# 4_Connectors.net
KiCad netlist of a schematic drawn in Altium Designer
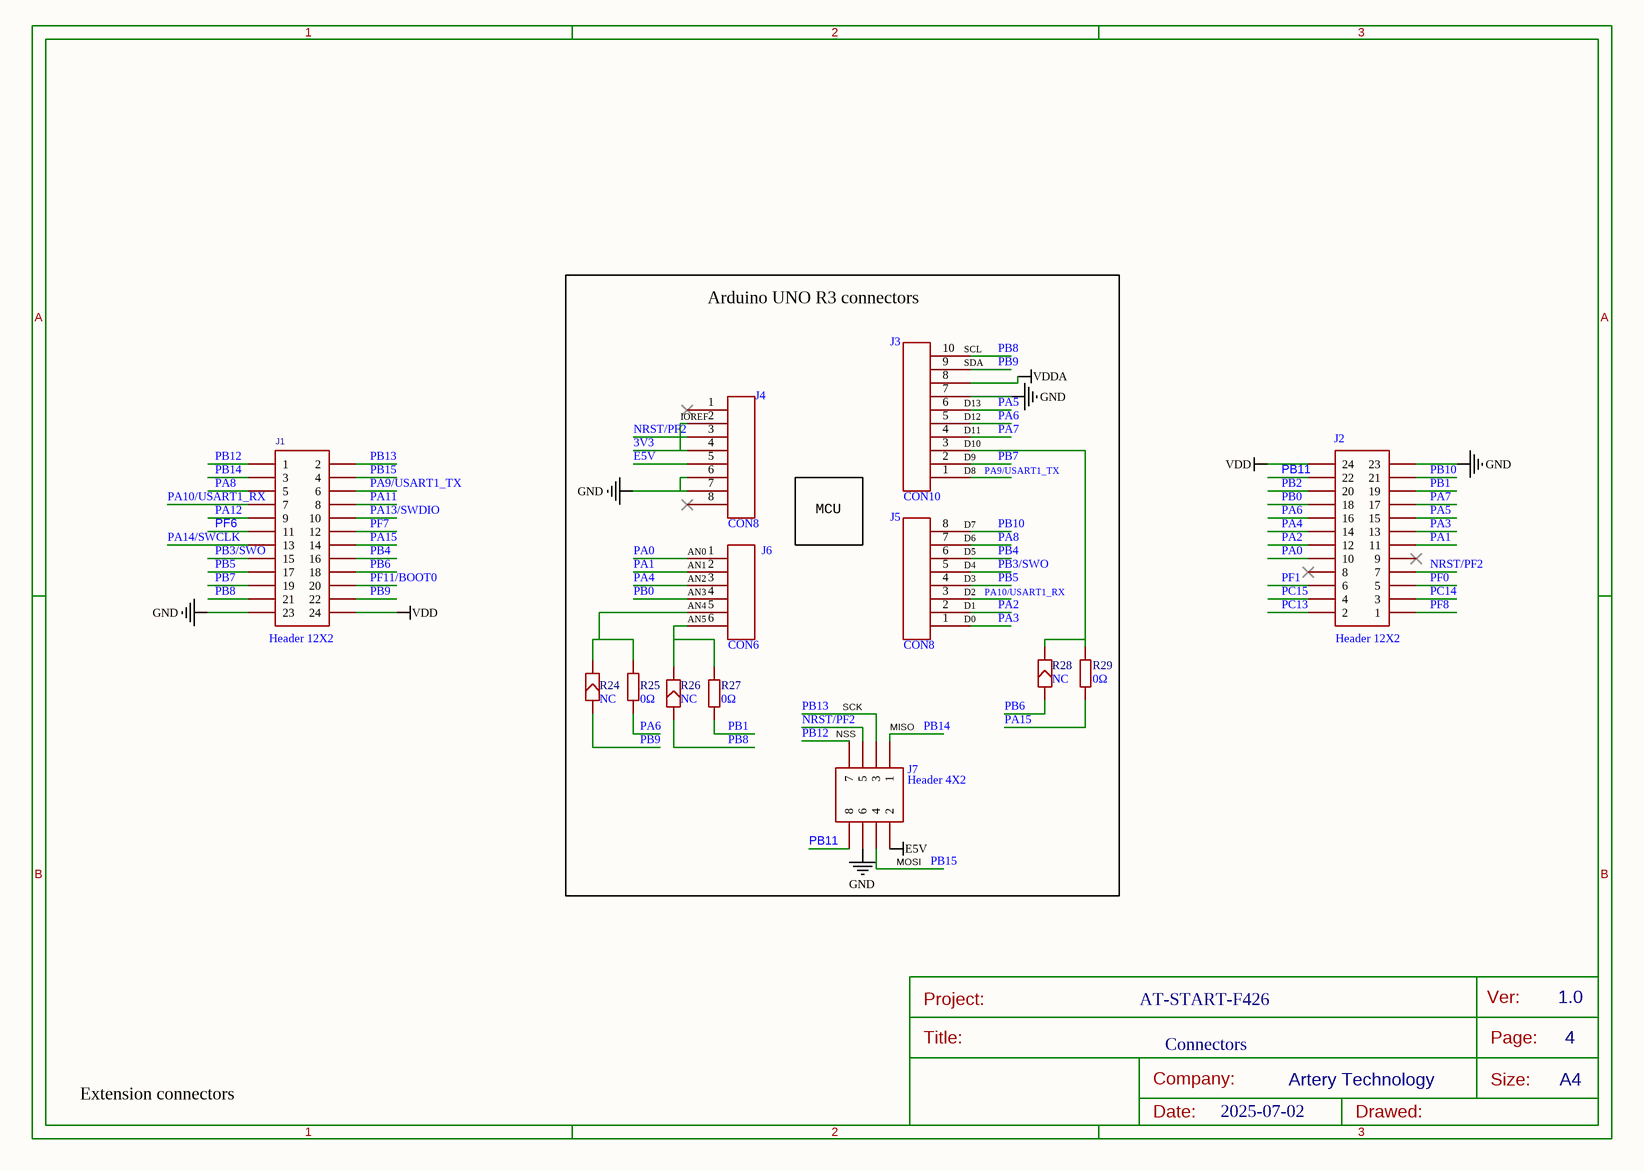
[diagram p0: 4_Connectors.schdoc]

(export (version "E")
  (design (tool "Eeschema 10.0.6"))
  (components
    (comp (ref "J1")
      (value "Header 12X2")
      (footprint "HEAD2*12")
      (fields (field (name "PUBLISHER") "Altium Limited"))
      (libsource (lib "altium-import") (part "root_0_Header 12X2_"))
    )
    (comp (ref "J2")
      (value "Header 12X2")
      (footprint "HEAD2*12")
      (fields (field (name "PUBLISHER") "Altium Limited"))
      (libsource (lib "altium-import") (part "root_2_Header 12X2_"))
    )
    (comp (ref "J3")
      (value "CON10")
      (footprint "HDR1X10 - 2#")
      (libsource (lib "altium-import") (part "root_2_CON10_"))
    )
    (comp (ref "J4")
      (value "CON8")
      (footprint "HDR1X8 - 2#")
      (libsource (lib "altium-import") (part "root_0_CON8_"))
    )
    (comp (ref "J5")
      (value "CON8")
      (footprint "HDR1X8 - 2#")
      (libsource (lib "altium-import") (part "root_2_CON8_"))
    )
    (comp (ref "J6")
      (value "CON6")
      (footprint "HDR1X6 -2#")
      (libsource (lib "altium-import") (part "root_0_CON6_"))
    )
    (comp (ref "J7")
      (value "Header 4X2")
      (footprint "HDR2X4")
      (fields (field (name "PUBLISHER") "Altium Limited"))
      (libsource (lib "altium-import") (part "root_3_Header 4X2_"))
    )
    (comp (ref "R24")
      (value "NC")
      (footprint "SB-PAD_2")
      (libsource (lib "altium-import") (part "root_1_SB_PAD_"))
    )
    (comp (ref "R25")
      (value "0Ω")
      (footprint "SB-PAD_2")
      (fields
        (field (name "MANUFACTURER") "UNI-ROYAL(厚声)")
        (field (name "MANUFACTURER PART") "0603WAF0000T5E")
        (field (name "TOLERANCE") "±1%")
      )
      (libsource (lib "altium-import") (part "root_1_0603WAF0000T5E_"))
    )
    (comp (ref "R26")
      (value "NC")
      (footprint "SB-PAD_2")
      (libsource (lib "altium-import") (part "root_1_SB_PAD_"))
    )
    (comp (ref "R27")
      (value "0Ω")
      (footprint "SB-PAD_2")
      (fields
        (field (name "MANUFACTURER") "UNI-ROYAL(厚声)")
        (field (name "MANUFACTURER PART") "0603WAF0000T5E")
        (field (name "TOLERANCE") "±1%")
      )
      (libsource (lib "altium-import") (part "root_1_0603WAF0000T5E_"))
    )
    (comp (ref "R28")
      (value "NC")
      (footprint "SB-PAD_2")
      (libsource (lib "altium-import") (part "root_1_SB_PAD_"))
    )
    (comp (ref "R29")
      (value "0Ω")
      (footprint "SB-PAD_2")
      (fields
        (field (name "MANUFACTURER") "UNI-ROYAL(厚声)")
        (field (name "MANUFACTURER PART") "0603WAF0000T5E")
        (field (name "TOLERANCE") "±1%")
      )
      (libsource (lib "altium-import") (part "root_1_0603WAF0000T5E_"))
    )
  )
  (nets
    (net (code "1") (name "/3V3") (class "Default")
      (node (ref "J4") (pin "2") (pinfunction "2_2") (pintype "passive"))
      (node (ref "J4") (pin "4") (pinfunction "4_4") (pintype "passive"))
    )
    (net (code "2") (name "/NRST{slash}PF2") (class "Default")
      (node (ref "J2") (pin "7") (pinfunction "7_7") (pintype "passive"))
      (node (ref "J4") (pin "3") (pinfunction "3_3") (pintype "passive"))
      (node (ref "J7") (pin "5") (pinfunction "5_5") (pintype "passive"))
    )
    (net (code "3") (name "/PA0") (class "Default")
      (node (ref "J2") (pin "10") (pinfunction "10_10") (pintype "passive"))
      (node (ref "J6") (pin "1") (pinfunction "1_1") (pintype "passive"))
    )
    (net (code "4") (name "/PA1") (class "Default")
      (node (ref "J2") (pin "11") (pinfunction "11_11") (pintype "passive"))
      (node (ref "J6") (pin "2") (pinfunction "2_2") (pintype "passive"))
    )
    (net (code "5") (name "/PA2") (class "Default")
      (node (ref "J2") (pin "12") (pinfunction "12_12") (pintype "passive"))
      (node (ref "J5") (pin "2") (pinfunction "2_2") (pintype "passive"))
    )
    (net (code "6") (name "/PA3") (class "Default")
      (node (ref "J2") (pin "13") (pinfunction "13_13") (pintype "passive"))
      (node (ref "J5") (pin "1") (pinfunction "1_1") (pintype "passive"))
    )
    (net (code "7") (name "/PA4") (class "Default")
      (node (ref "J2") (pin "14") (pinfunction "14_14") (pintype "passive"))
      (node (ref "J6") (pin "3") (pinfunction "3_3") (pintype "passive"))
    )
    (net (code "8") (name "/PA5") (class "Default")
      (node (ref "J2") (pin "15") (pinfunction "15_15") (pintype "passive"))
      (node (ref "J3") (pin "6") (pinfunction "6_6") (pintype "passive"))
    )
    (net (code "9") (name "/PA6") (class "Default")
      (node (ref "J2") (pin "16") (pinfunction "16_16") (pintype "passive"))
      (node (ref "J3") (pin "5") (pinfunction "5_5") (pintype "passive"))
      (node (ref "R25") (pin "1") (pinfunction "1_1") (pintype "passive"))
    )
    (net (code "10") (name "/PA7") (class "Default")
      (node (ref "J2") (pin "17") (pinfunction "17_17") (pintype "passive"))
      (node (ref "J3") (pin "4") (pinfunction "4_4") (pintype "passive"))
    )
    (net (code "11") (name "/PA8") (class "Default")
      (node (ref "J1") (pin "5") (pinfunction "5_5") (pintype "passive"))
      (node (ref "J5") (pin "7") (pinfunction "7_7") (pintype "passive"))
    )
    (net (code "12") (name "/PA9{slash}USART1_TX") (class "Default")
      (node (ref "J1") (pin "6") (pinfunction "6_6") (pintype "passive"))
      (node (ref "J3") (pin "1") (pinfunction "1_1") (pintype "passive"))
    )
    (net (code "13") (name "/PA10{slash}USART1_RX") (class "Default")
      (node (ref "J1") (pin "7") (pinfunction "7_7") (pintype "passive"))
      (node (ref "J5") (pin "3") (pinfunction "3_3") (pintype "passive"))
    )
    (net (code "14") (name "/PA11") (class "Default")
      (node (ref "J1") (pin "8") (pinfunction "8_8") (pintype "passive"))
    )
    (net (code "15") (name "/PA12") (class "Default")
      (node (ref "J1") (pin "9") (pinfunction "9_9") (pintype "passive"))
    )
    (net (code "16") (name "/PA13{slash}SWDIO") (class "Default")
      (node (ref "J1") (pin "10") (pinfunction "10_10") (pintype "passive"))
    )
    (net (code "17") (name "/PA14{slash}SWCLK") (class "Default")
      (node (ref "J1") (pin "13") (pinfunction "13_13") (pintype "passive"))
    )
    (net (code "18") (name "/PA15") (class "Default")
      (node (ref "J1") (pin "14") (pinfunction "14_14") (pintype "passive"))
      (node (ref "R29") (pin "1") (pinfunction "1_1") (pintype "passive"))
    )
    (net (code "19") (name "/PB0") (class "Default")
      (node (ref "J2") (pin "18") (pinfunction "18_18") (pintype "passive"))
      (node (ref "J6") (pin "4") (pinfunction "4_4") (pintype "passive"))
    )
    (net (code "20") (name "/PB1") (class "Default")
      (node (ref "J2") (pin "19") (pinfunction "19_19") (pintype "passive"))
      (node (ref "R27") (pin "1") (pinfunction "1_1") (pintype "passive"))
    )
    (net (code "21") (name "/PB2") (class "Default")
      (node (ref "J2") (pin "20") (pinfunction "20_20") (pintype "passive"))
    )
    (net (code "22") (name "/PB3{slash}SWO") (class "Default")
      (node (ref "J1") (pin "15") (pinfunction "15_15") (pintype "passive"))
      (node (ref "J5") (pin "5") (pinfunction "5_5") (pintype "passive"))
    )
    (net (code "23") (name "/PB4") (class "Default")
      (node (ref "J1") (pin "16") (pinfunction "16_16") (pintype "passive"))
      (node (ref "J5") (pin "6") (pinfunction "6_6") (pintype "passive"))
    )
    (net (code "24") (name "/PB5") (class "Default")
      (node (ref "J1") (pin "17") (pinfunction "17_17") (pintype "passive"))
      (node (ref "J5") (pin "4") (pinfunction "4_4") (pintype "passive"))
    )
    (net (code "25") (name "/PB6") (class "Default")
      (node (ref "J1") (pin "18") (pinfunction "18_18") (pintype "passive"))
      (node (ref "R28") (pin "1") (pinfunction "1_1") (pintype "passive"))
    )
    (net (code "26") (name "/PB7") (class "Default")
      (node (ref "J1") (pin "19") (pinfunction "19_19") (pintype "passive"))
      (node (ref "J3") (pin "2") (pinfunction "2_2") (pintype "passive"))
    )
    (net (code "27") (name "/PB8") (class "Default")
      (node (ref "J1") (pin "21") (pinfunction "21_21") (pintype "passive"))
      (node (ref "J3") (pin "10") (pinfunction "10_10") (pintype "passive"))
      (node (ref "R26") (pin "1") (pinfunction "1_1") (pintype "passive"))
    )
    (net (code "28") (name "/PB9") (class "Default")
      (node (ref "J1") (pin "22") (pinfunction "22_22") (pintype "passive"))
      (node (ref "J3") (pin "9") (pinfunction "9_9") (pintype "passive"))
      (node (ref "R24") (pin "1") (pinfunction "1_1") (pintype "passive"))
    )
    (net (code "29") (name "/PB10") (class "Default")
      (node (ref "J2") (pin "21") (pinfunction "21_21") (pintype "passive"))
      (node (ref "J5") (pin "8") (pinfunction "8_8") (pintype "passive"))
    )
    (net (code "30") (name "/PB11") (class "Default")
      (node (ref "J2") (pin "22") (pinfunction "22_22") (pintype "passive"))
      (node (ref "J7") (pin "8") (pinfunction "8_8") (pintype "passive"))
    )
    (net (code "31") (name "/PB12") (class "Default")
      (node (ref "J1") (pin "1") (pinfunction "1_1") (pintype "passive"))
      (node (ref "J7") (pin "7") (pinfunction "7_7") (pintype "passive"))
    )
    (net (code "32") (name "/PB13") (class "Default")
      (node (ref "J1") (pin "2") (pinfunction "2_2") (pintype "passive"))
      (node (ref "J7") (pin "3") (pinfunction "3_3") (pintype "passive"))
    )
    (net (code "33") (name "/PB14") (class "Default")
      (node (ref "J1") (pin "3") (pinfunction "3_3") (pintype "passive"))
      (node (ref "J7") (pin "1") (pinfunction "1_1") (pintype "passive"))
    )
    (net (code "34") (name "/PB15") (class "Default")
      (node (ref "J1") (pin "4") (pinfunction "4_4") (pintype "passive"))
      (node (ref "J7") (pin "4") (pinfunction "4_4") (pintype "passive"))
    )
    (net (code "35") (name "/PC13") (class "Default")
      (node (ref "J2") (pin "2") (pinfunction "2_2") (pintype "passive"))
    )
    (net (code "36") (name "/PC14") (class "Default")
      (node (ref "J2") (pin "3") (pinfunction "3_3") (pintype "passive"))
    )
    (net (code "37") (name "/PC15") (class "Default")
      (node (ref "J2") (pin "4") (pinfunction "4_4") (pintype "passive"))
    )
    (net (code "38") (name "/PF0") (class "Default")
      (node (ref "J2") (pin "5") (pinfunction "5_5") (pintype "passive"))
    )
    (net (code "39") (name "/PF1") (class "Default")
      (node (ref "J2") (pin "6") (pinfunction "6_6") (pintype "passive"))
    )
    (net (code "40") (name "/PF6") (class "Default")
      (node (ref "J1") (pin "11") (pinfunction "11_11") (pintype "passive"))
    )
    (net (code "41") (name "/PF7") (class "Default")
      (node (ref "J1") (pin "12") (pinfunction "12_12") (pintype "passive"))
    )
    (net (code "42") (name "/PF8") (class "Default")
      (node (ref "J2") (pin "1") (pinfunction "1_1") (pintype "passive"))
    )
    (net (code "43") (name "/PF11{slash}BOOT0") (class "Default")
      (node (ref "J1") (pin "20") (pinfunction "20_20") (pintype "passive"))
    )
    (net (code "44") (name "E5V") (class "Default")
      (node (ref "J4") (pin "5") (pinfunction "5_5") (pintype "passive"))
      (node (ref "J7") (pin "2") (pinfunction "2_2") (pintype "passive"))
    )
    (net (code "45") (name "GND") (class "Default")
      (node (ref "J1") (pin "23") (pinfunction "23_23") (pintype "passive"))
      (node (ref "J2") (pin "23") (pinfunction "23_23") (pintype "passive"))
      (node (ref "J3") (pin "7") (pinfunction "7_7") (pintype "passive"))
      (node (ref "J4") (pin "6") (pinfunction "6_6") (pintype "passive"))
      (node (ref "J4") (pin "7") (pinfunction "7_7") (pintype "passive"))
      (node (ref "J7") (pin "6") (pinfunction "6_6") (pintype "passive"))
    )
    (net (code "46") (name "Net-(J3-Pad3)") (class "Default")
      (node (ref "J3") (pin "3") (pinfunction "3_3") (pintype "passive"))
      (node (ref "R28") (pin "2") (pinfunction "2_2") (pintype "passive"))
      (node (ref "R29") (pin "2") (pinfunction "2_2") (pintype "passive"))
    )
    (net (code "47") (name "Net-(J6-Pad5)") (class "Default")
      (node (ref "J6") (pin "5") (pinfunction "5_5") (pintype "passive"))
      (node (ref "R24") (pin "2") (pinfunction "2_2") (pintype "passive"))
      (node (ref "R25") (pin "2") (pinfunction "2_2") (pintype "passive"))
    )
    (net (code "48") (name "Net-(J6-Pad6)") (class "Default")
      (node (ref "J6") (pin "6") (pinfunction "6_6") (pintype "passive"))
      (node (ref "R26") (pin "2") (pinfunction "2_2") (pintype "passive"))
      (node (ref "R27") (pin "2") (pinfunction "2_2") (pintype "passive"))
    )
    (net (code "49") (name "VDD") (class "Default")
      (node (ref "J1") (pin "24") (pinfunction "24_24") (pintype "passive"))
      (node (ref "J2") (pin "24") (pinfunction "24_24") (pintype "passive"))
    )
    (net (code "50") (name "VDDA") (class "Default")
      (node (ref "J3") (pin "8") (pinfunction "8_8") (pintype "passive"))
    )
    (net (code "51") (name "unconnected-(J2-Pad8)") (class "Default")
      (node (ref "J2") (pin "8") (pinfunction "8_8") (pintype "passive+no_connect"))
    )
    (net (code "52") (name "unconnected-(J2-Pad9)") (class "Default")
      (node (ref "J2") (pin "9") (pinfunction "9_9") (pintype "passive+no_connect"))
    )
    (net (code "53") (name "unconnected-(J4-Pad1)") (class "Default")
      (node (ref "J4") (pin "1") (pinfunction "1_1") (pintype "passive+no_connect"))
    )
    (net (code "54") (name "unconnected-(J4-Pad8)") (class "Default")
      (node (ref "J4") (pin "8") (pinfunction "8_8") (pintype "passive+no_connect"))
    )
  )
)
